# SWD.net
KiCad netlist of a schematic drawn in Altium Designer
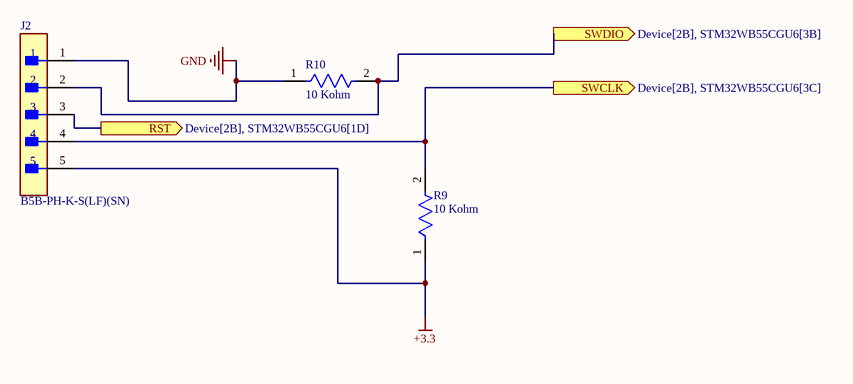
[diagram p0: SWD.SchDoc]

(export (version "E")
  (design (tool "Eeschema 10.0.6"))
  (components
    (comp (ref "J2")
      (value "B5B-PH-K-S(LF)(SN)")
      (footprint "FP-B5B-PH-K-S_LF_SN-MFG")
      (description "CONN HEADER VERT 5POS 2MM")
      (libsource (lib "Altium Content Vault") (part "bf93c07fd2649a848d0ec8585582aab"))
    )
    (comp (ref "R9")
      (value "10 Kohm")
      (footprint "FP-RC1005-IPC_C")
      (description "Res Thick Film 0402 1.87kΩ 1% 0.063W ±100ppm/°C Molded SMD T/R")
      (fields (field (name "TOLERANCE") "1%"))
      (libsource (lib "Altium Content Vault") (part "1029c3af85768c4190bb7ad29bc67b5"))
    )
    (comp (ref "R10")
      (value "10 Kohm")
      (footprint "FP-RC1005-IPC_C")
      (description "Res Thick Film 0402 1.87kΩ 1% 0.063W ±100ppm/°C Molded SMD T/R")
      (fields (field (name "TOLERANCE") "1%"))
      (libsource (lib "Altium Content Vault") (part "1029c3af85768c4190bb7ad29bc67b5"))
    )
  )
  (nets
    (net (code "1") (name "+3.3") (class "Default")
      (node (ref "J2") (pin "5") (pinfunction "5_5") (pintype "passive"))
      (node (ref "R9") (pin "1") (pinfunction "1_1") (pintype "passive"))
    )
    (net (code "2") (name "/RST") (class "Default")
      (node (ref "J2") (pin "3") (pinfunction "3_3") (pintype "passive"))
    )
    (net (code "3") (name "/SWCLK") (class "Default")
      (node (ref "J2") (pin "4") (pinfunction "4_4") (pintype "passive"))
      (node (ref "R9") (pin "2") (pinfunction "2_2") (pintype "passive"))
    )
    (net (code "4") (name "/SWDIO") (class "Default")
      (node (ref "J2") (pin "2") (pinfunction "2_2") (pintype "passive"))
      (node (ref "R10") (pin "2") (pinfunction "2_2") (pintype "passive"))
    )
    (net (code "5") (name "GND") (class "Default")
      (node (ref "J2") (pin "1") (pinfunction "1_1") (pintype "passive"))
      (node (ref "R10") (pin "1") (pinfunction "1_1") (pintype "passive"))
    )
  )
)
